# CW308T_K24_UFO.net
KiCad netlist of a schematic drawn in Altium Designer
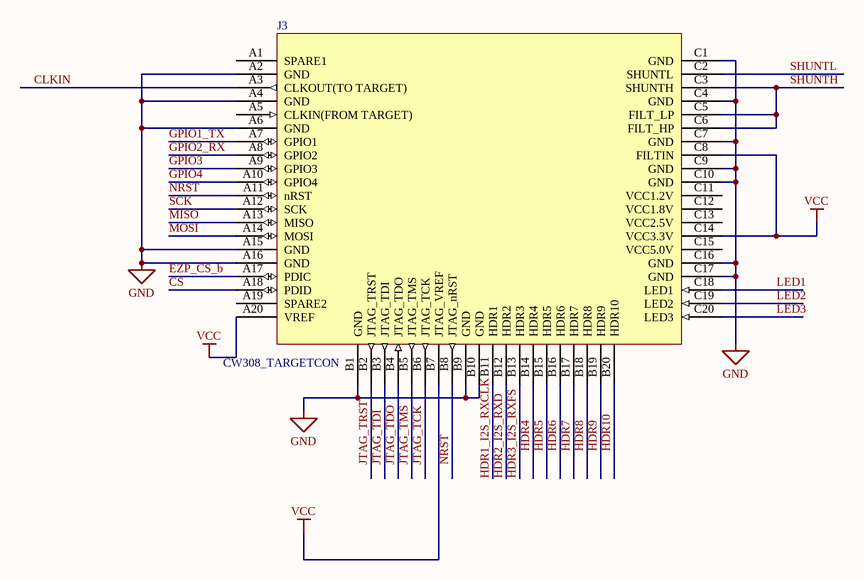
[diagram p0: CW308T_K24_UFO.SchDoc]

(export (version "E")
  (design (tool "Eeschema 10.0.6"))
  (components
    (comp (ref "J3")
      (value "CW308_TARGETCON")
      (footprint "CW308_TBOARD_CONN")
      (description "CW308 \"Standard\" Target Board Connector")
      (fields (field (name "PART NUMBER") "CW308_TBOARD"))
      (libsource (lib "NewAE_AltiumLib") (part "CW308_TBOARD"))
    )
  )
  (nets
    (net (code "1") (name "/CLKIN") (class "Default")
      (node (ref "J3") (pin "A3") (pinfunction "CLKOUT(TO_TARGET)_A3") (pintype "output"))
    )
    (net (code "2") (name "/CS") (class "Default")
      (node (ref "J3") (pin "A18") (pinfunction "PDID_A18") (pintype "bidirectional"))
    )
    (net (code "3") (name "/EZP_CS_b") (class "Default")
      (node (ref "J3") (pin "A17") (pinfunction "PDIC_A17") (pintype "bidirectional"))
    )
    (net (code "4") (name "/GPIO1_TX") (class "Default")
      (node (ref "J3") (pin "A7") (pinfunction "GPIO1_A7") (pintype "bidirectional"))
    )
    (net (code "5") (name "/GPIO2_RX") (class "Default")
      (node (ref "J3") (pin "A8") (pinfunction "GPIO2_A8") (pintype "bidirectional"))
    )
    (net (code "6") (name "/GPIO3") (class "Default")
      (node (ref "J3") (pin "A9") (pinfunction "GPIO3_A9") (pintype "bidirectional"))
    )
    (net (code "7") (name "/GPIO4") (class "Default")
      (node (ref "J3") (pin "A10") (pinfunction "GPIO4_A10") (pintype "bidirectional"))
    )
    (net (code "8") (name "/HDR1_I2S_RXCLK") (class "Default")
      (node (ref "J3") (pin "B11") (pinfunction "HDR1_B11") (pintype "passive"))
    )
    (net (code "9") (name "/HDR2_I2S_RXD") (class "Default")
      (node (ref "J3") (pin "B12") (pinfunction "HDR2_B12") (pintype "passive"))
    )
    (net (code "10") (name "/HDR3_I2S_RXFS") (class "Default")
      (node (ref "J3") (pin "B13") (pinfunction "HDR3_B13") (pintype "passive"))
    )
    (net (code "11") (name "/HDR4") (class "Default")
      (node (ref "J3") (pin "B14") (pinfunction "HDR4_B14") (pintype "passive"))
    )
    (net (code "12") (name "/HDR5") (class "Default")
      (node (ref "J3") (pin "B15") (pinfunction "HDR5_B15") (pintype "passive"))
    )
    (net (code "13") (name "/HDR6") (class "Default")
      (node (ref "J3") (pin "B16") (pinfunction "HDR6_B16") (pintype "passive"))
    )
    (net (code "14") (name "/HDR7") (class "Default")
      (node (ref "J3") (pin "B17") (pinfunction "HDR7_B17") (pintype "passive"))
    )
    (net (code "15") (name "/HDR8") (class "Default")
      (node (ref "J3") (pin "B18") (pinfunction "HDR8_B18") (pintype "passive"))
    )
    (net (code "16") (name "/HDR9") (class "Default")
      (node (ref "J3") (pin "B19") (pinfunction "HDR9_B19") (pintype "passive"))
    )
    (net (code "17") (name "/HDR10") (class "Default")
      (node (ref "J3") (pin "B20") (pinfunction "HDR10_B20") (pintype "passive"))
    )
    (net (code "18") (name "/JTAG_TCK") (class "Default")
      (node (ref "J3") (pin "B6") (pinfunction "JTAG_TCK_B6") (pintype "output"))
    )
    (net (code "19") (name "/JTAG_TDI") (class "Default")
      (node (ref "J3") (pin "B3") (pinfunction "JTAG_TDI_B3") (pintype "output"))
    )
    (net (code "20") (name "/JTAG_TDO") (class "Default")
      (node (ref "J3") (pin "B4") (pinfunction "JTAG_TDO_B4") (pintype "input"))
    )
    (net (code "21") (name "/JTAG_TMS") (class "Default")
      (node (ref "J3") (pin "B5") (pinfunction "JTAG_TMS_B5") (pintype "output"))
    )
    (net (code "22") (name "/JTAG_TRST") (class "Default")
      (node (ref "J3") (pin "B2") (pinfunction "JTAG_TRST_B2") (pintype "output"))
    )
    (net (code "23") (name "/LED1") (class "Default")
      (node (ref "J3") (pin "C18") (pinfunction "LED1_C18") (pintype "input"))
    )
    (net (code "24") (name "/LED2") (class "Default")
      (node (ref "J3") (pin "C19") (pinfunction "LED2_C19") (pintype "input"))
    )
    (net (code "25") (name "/LED3") (class "Default")
      (node (ref "J3") (pin "C20") (pinfunction "LED3_C20") (pintype "input"))
    )
    (net (code "26") (name "/MISO") (class "Default")
      (node (ref "J3") (pin "A13") (pinfunction "MISO_A13") (pintype "bidirectional"))
    )
    (net (code "27") (name "/MOSI") (class "Default")
      (node (ref "J3") (pin "A14") (pinfunction "MOSI_A14") (pintype "bidirectional"))
    )
    (net (code "28") (name "/NRST") (class "Default")
      (node (ref "J3") (pin "A11") (pinfunction "nRST_A11") (pintype "bidirectional"))
      (node (ref "J3") (pin "B8") (pinfunction "JTAG_nRST_B8") (pintype "output"))
    )
    (net (code "29") (name "/SCK") (class "Default")
      (node (ref "J3") (pin "A12") (pinfunction "SCK_A12") (pintype "bidirectional"))
    )
    (net (code "30") (name "/SHUNTH") (class "Default")
      (node (ref "J3") (pin "C3") (pinfunction "SHUNTH_C3") (pintype "passive"))
      (node (ref "J3") (pin "C5") (pinfunction "FILT_LP_C5") (pintype "passive"))
      (node (ref "J3") (pin "C6") (pinfunction "FILT_HP_C6") (pintype "passive"))
    )
    (net (code "31") (name "/SHUNTL") (class "Default")
      (node (ref "J3") (pin "C2") (pinfunction "SHUNTL_C2") (pintype "passive"))
    )
    (net (code "32") (name "GND") (class "Default")
      (node (ref "J3") (pin "A15") (pinfunction "GND_A15") (pintype "passive"))
      (node (ref "J3") (pin "A16") (pinfunction "GND_A16") (pintype "passive"))
      (node (ref "J3") (pin "A2") (pinfunction "GND_A2") (pintype "passive"))
      (node (ref "J3") (pin "A4") (pinfunction "GND_A4") (pintype "passive"))
      (node (ref "J3") (pin "A6") (pinfunction "GND_A6") (pintype "power_in"))
      (node (ref "J3") (pin "B1") (pinfunction "GND_B1") (pintype "passive"))
      (node (ref "J3") (pin "B10") (pinfunction "GND_B10") (pintype "passive"))
      (node (ref "J3") (pin "B9") (pinfunction "GND_B9") (pintype "passive"))
      (node (ref "J3") (pin "C1") (pinfunction "GND_C1") (pintype "power_in"))
      (node (ref "J3") (pin "C10") (pinfunction "GND_C10") (pintype "power_in"))
      (node (ref "J3") (pin "C16") (pinfunction "GND_C16") (pintype "power_in"))
      (node (ref "J3") (pin "C17") (pinfunction "GND_C17") (pintype "power_in"))
      (node (ref "J3") (pin "C4") (pinfunction "GND_C4") (pintype "power_in"))
      (node (ref "J3") (pin "C7") (pinfunction "GND_C7") (pintype "power_in"))
      (node (ref "J3") (pin "C9") (pinfunction "GND_C9") (pintype "power_in"))
    )
    (net (code "33") (name "VCC") (class "Default")
      (node (ref "J3") (pin "A20") (pinfunction "VREF_A20") (pintype "tri_state"))
      (node (ref "J3") (pin "B7") (pinfunction "JTAG_VREF_B7") (pintype "tri_state"))
      (node (ref "J3") (pin "C14") (pinfunction "VCC3.3V_C14") (pintype "power_in"))
      (node (ref "J3") (pin "C8") (pinfunction "FILTIN_C8") (pintype "passive"))
    )
    (net (code "34") (name "unconnected-(J3-CLKIN(FROM_TARGET)-PadA5)") (class "Default")
      (node (ref "J3") (pin "A5") (pinfunction "CLKIN(FROM_TARGET)_A5") (pintype "input"))
    )
    (net (code "35") (name "unconnected-(J3-SPARE1-PadA1)") (class "Default")
      (node (ref "J3") (pin "A1") (pinfunction "SPARE1_A1") (pintype "passive"))
    )
    (net (code "36") (name "unconnected-(J3-SPARE2-PadA19)") (class "Default")
      (node (ref "J3") (pin "A19") (pinfunction "SPARE2_A19") (pintype "passive"))
    )
    (net (code "37") (name "unconnected-(J3-VCC1.2V-PadC11)") (class "Default")
      (node (ref "J3") (pin "C11") (pinfunction "VCC1.2V_C11") (pintype "power_in"))
    )
    (net (code "38") (name "unconnected-(J3-VCC1.8V-PadC12)") (class "Default")
      (node (ref "J3") (pin "C12") (pinfunction "VCC1.8V_C12") (pintype "power_in"))
    )
    (net (code "39") (name "unconnected-(J3-VCC2.5V-PadC13)") (class "Default")
      (node (ref "J3") (pin "C13") (pinfunction "VCC2.5V_C13") (pintype "power_in"))
    )
    (net (code "40") (name "unconnected-(J3-VCC5.0V-PadC15)") (class "Default")
      (node (ref "J3") (pin "C15") (pinfunction "VCC5.0V_C15") (pintype "power_in"))
    )
  )
)
